# source_iref_gen.net
KiCad netlist of a schematic drawn in Altium Designer
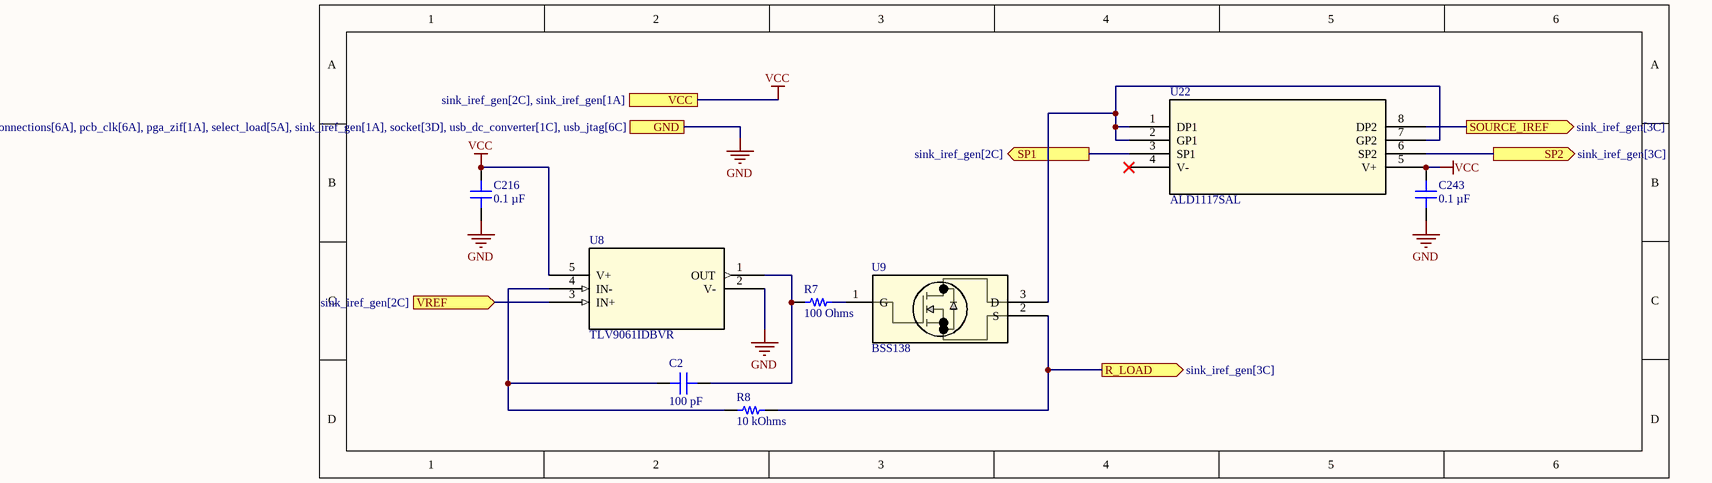
[diagram p0: source_iref_gen.SchDoc]

(export (version "E")
  (design (tool "Eeschema 10.0.6"))
  (components
    (comp (ref "C2")
      (value "100 pF")
      (footprint "CAP 0805_2012")
      (description "CAP CER 100PF 50V C0G/NP0 0805")
      (fields
        (field (name "PART NUMBER") "500R15N101JV4T")
        (field (name "CAPACITANCE") "100 pF")
        (field (name "MANUFACTURER") "Johanson Dielectrics Inc.")
      )
      (libsource (lib "Celestial Altium Library - altium_library") (part "Capacitor"))
    )
    (comp (ref "C216")
      (value "0.1 µF")
      (footprint "CAP 0805_2012")
      (description "CAP CER 0.1UF 16V X7R 0805")
      (fields
        (field (name "PART NUMBER") "160R15W104KV4T")
        (field (name "CAPACITANCE") "0.1 µF")
        (field (name "MANUFACTURER") "Johanson Dielectrics Inc.")
      )
      (libsource (lib "Celestial Altium Library - altium_library") (part "Capacitor"))
    )
    (comp (ref "C243")
      (value "0.1 µF")
      (footprint "CAP 0805_2012")
      (description "CAP CER 0.1UF 16V X7R 0805")
      (fields
        (field (name "PART NUMBER") "160R15W104KV4T")
        (field (name "CAPACITANCE") "0.1 µF")
        (field (name "MANUFACTURER") "Johanson Dielectrics Inc.")
      )
      (libsource (lib "Celestial Altium Library - altium_library") (part "Capacitor"))
    )
    (comp (ref "R7")
      (value "100 Ohms")
      (footprint "RES 0805_2012")
      (description "RES SMD 100 OHM 1% 3/4W 0805")
      (fields (field (name "PART NUMBER") "RCS0805100RFKEA") (field (name "MANUFACTURER") "Vishay Dale"))
      (libsource (lib "Celestial Altium Library - altium_library") (part "Resistor"))
    )
    (comp (ref "R8")
      (value "10 kOhms")
      (footprint "RES 0805_2012")
      (description "RES 10K OHM 0.1% 1/10W 0805")
      (fields
        (field (name "PART NUMBER") "RNCS0805BKE10K0")
        (field (name "MANUFACTURER") "Stackpole Electronics Inc")
      )
      (libsource (lib "Celestial Altium Library - altium_library") (part "Resistor"))
    )
    (comp (ref "U8")
      (value "TLV9061IDBVR")
      (footprint "DBV5_TEX")
      (fields (field (name "COPYRIGHT") "Copyright (C) 2026 Ultra Librarian. All rights reserved."))
      (libsource (lib "OpAmps") (part "TLV9061IDBVR"))
    )
    (comp (ref "U9")
      (value "BSS138")
      (footprint "SOT-23_3L_ONS")
      (description "Description")
      (fields (field (name "COPYRIGHT") "Copyright (C) 2025 Ultra Librarian. All rights reserved."))
      (libsource (lib "Mosfets") (part "BSS138"))
    )
    (comp (ref "U22")
      (value "ALD1117SAL")
      (footprint "8-SOIC_ALD")
      (description "No Description Available")
      (fields (field (name "COPYRIGHT") "Copyright (C) 2026 Ultra Librarian. All rights reserved."))
      (libsource (lib "Mosfets") (part "ALD1117SAL"))
    )
  )
  (nets
    (net (code "1") (name "/R_LOAD") (class "Default")
      (node (ref "R8") (pin "2") (pinfunction "2_2") (pintype "passive"))
      (node (ref "U9") (pin "2") (pinfunction "S_2") (pintype "passive"))
    )
    (net (code "2") (name "/SOURCE_IREF") (class "Default")
      (node (ref "U22") (pin "8") (pinfunction "DP2_8") (pintype "passive"))
    )
    (net (code "3") (name "/SP1") (class "Default")
      (node (ref "U22") (pin "3") (pinfunction "SP1_3") (pintype "passive"))
    )
    (net (code "4") (name "/SP2") (class "Default")
      (node (ref "U22") (pin "6") (pinfunction "SP2_6") (pintype "passive"))
    )
    (net (code "5") (name "/VREF") (class "Default")
      (node (ref "U8") (pin "3") (pinfunction "IN+_3") (pintype "input"))
    )
    (net (code "6") (name "GND") (class "Default")
      (node (ref "C216") (pin "1") (pinfunction "1_1") (pintype "passive"))
      (node (ref "C243") (pin "1") (pinfunction "1_1") (pintype "passive"))
      (node (ref "U8") (pin "2") (pinfunction "V-_2") (pintype "power_in"))
    )
    (net (code "7") (name "Net-(U8-IN-)") (class "Default")
      (node (ref "C2") (pin "1") (pinfunction "1_1") (pintype "passive"))
      (node (ref "R8") (pin "1") (pinfunction "1_1") (pintype "passive"))
      (node (ref "U8") (pin "4") (pinfunction "IN-_4") (pintype "input"))
    )
    (net (code "8") (name "Net-(U8-OUT)") (class "Default")
      (node (ref "C2") (pin "2") (pinfunction "2_2") (pintype "passive"))
      (node (ref "R7") (pin "2") (pinfunction "2_2") (pintype "passive"))
      (node (ref "U8") (pin "1") (pinfunction "OUT_1") (pintype "output"))
    )
    (net (code "9") (name "Net-(U9-G)") (class "Default")
      (node (ref "R7") (pin "1") (pinfunction "1_1") (pintype "passive"))
      (node (ref "U9") (pin "1") (pinfunction "G_1") (pintype "passive"))
    )
    (net (code "10") (name "Net-(U22-DP1)") (class "Default")
      (node (ref "U22") (pin "1") (pinfunction "DP1_1") (pintype "passive"))
      (node (ref "U22") (pin "2") (pinfunction "GP1_2") (pintype "passive"))
      (node (ref "U22") (pin "7") (pinfunction "GP2_7") (pintype "passive"))
      (node (ref "U9") (pin "3") (pinfunction "D_3") (pintype "passive"))
    )
    (net (code "11") (name "VCC") (class "Default")
      (node (ref "C216") (pin "2") (pinfunction "2_2") (pintype "passive"))
      (node (ref "C243") (pin "2") (pinfunction "2_2") (pintype "passive"))
      (node (ref "U22") (pin "5") (pinfunction "V+_5") (pintype "power_in"))
      (node (ref "U8") (pin "5") (pinfunction "V+_5") (pintype "power_in"))
    )
    (net (code "12") (name "unconnected-(U22-V--Pad4)") (class "Default")
      (node (ref "U22") (pin "4") (pinfunction "V-_4") (pintype "power_in+no_connect"))
    )
  )
)
